# ap3036b-boost-driver-mk-1_0.net
KiCad netlist of a schematic drawn in EAGLE
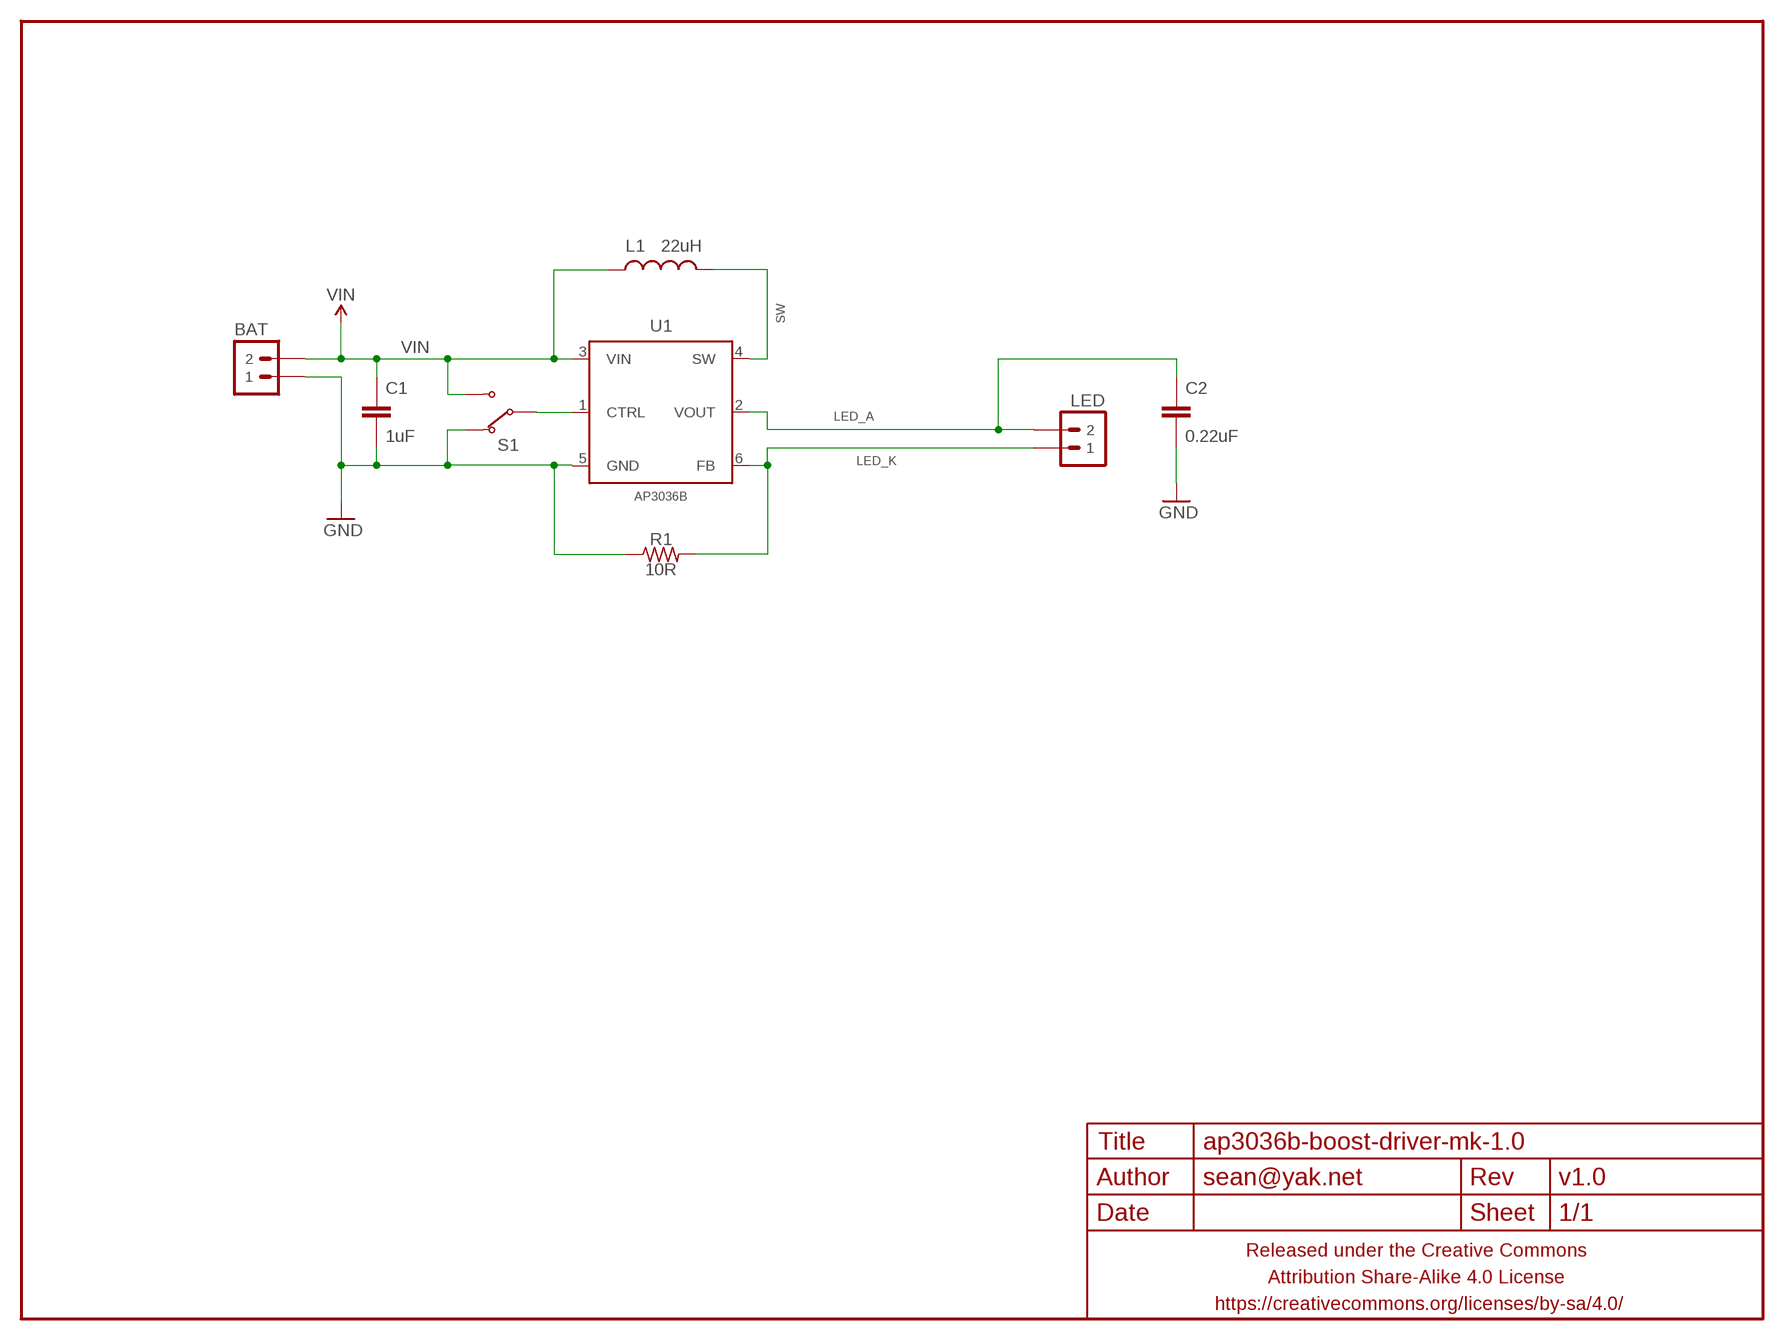
[diagram p0: schematic, sheet 1]

(export (version "E")
  (design (tool "Eeschema 10.0.6"))
  (components
    (comp (ref "BAT")
      (value "M02PTH-CENTERED")
      (footprint "eagle-import:1X02-CENTER")
      (libsource (lib "eagle-import") (part "M02PTH-CENTERED"))
    )
    (comp (ref "C1")
      (value "1uF")
      (footprint "eagle-import:C0603-TIGHTER")
      (libsource (lib "eagle-import") (part "CAPACITOR-CERAMICC0603-TIGHTER"))
    )
    (comp (ref "C2")
      (value "0.22uF")
      (footprint "eagle-import:C0603-TIGHTER")
      (libsource (lib "eagle-import") (part "CAPACITOR-CERAMICC0603-TIGHTER"))
    )
    (comp (ref "FRAME1")
      (value "FRAME-LETTERNO_PACKAGE")
      (footprint "eagle-import:DUMMY")
      (fields (field (name "DESIGNER") "sean@yak.net") (field (name "VERSION") "v1.0"))
      (libsource (lib "eagle-import") (part "FRAME-LETTERNO_PACKAGE"))
    )
    (comp (ref "L1")
      (value "22uH")
      (footprint "eagle-import:L0603")
      (libsource (lib "eagle-import") (part "INDUCTOR0603-TIGHTER"))
    )
    (comp (ref "LED")
      (value "M02PTH-CENTERED")
      (footprint "eagle-import:1X02-CENTER")
      (libsource (lib "eagle-import") (part "M02PTH-CENTERED"))
    )
    (comp (ref "R1")
      (value "10R")
      (footprint "eagle-import:R0603-TIGHTER")
      (libsource (lib "eagle-import") (part "RESISTORR0603-TIGHTER"))
    )
    (comp (ref "S1")
      (value "SWITCH-SPDTJS102011SAQN")
      (footprint "eagle-import:SWITCH-SPDT-SMD-RA-JS102011SAQN")
      (libsource (lib "eagle-import") (part "SWITCH-SPDTJS102011SAQN"))
    )
    (comp (ref "U1")
      (value "AP3036B")
      (footprint "eagle-import:SOT26")
      (libsource (lib "eagle-import") (part "AP3036B"))
    )
  )
  (nets
    (net (code "1") (name "/LED_A") (class "Default")
      (node (ref "C2") (pin "1") (pinfunction "1_1") (pintype "passive"))
      (node (ref "LED") (pin "2") (pinfunction "2_2") (pintype "passive"))
      (node (ref "U1") (pin "2") (pinfunction "VOUT_2") (pintype "bidirectional"))
    )
    (net (code "2") (name "/LED_K") (class "Default")
      (node (ref "LED") (pin "1") (pinfunction "1_1") (pintype "passive"))
      (node (ref "R1") (pin "2") (pinfunction "2_2") (pintype "passive"))
      (node (ref "U1") (pin "6") (pinfunction "FB_6") (pintype "bidirectional"))
    )
    (net (code "3") (name "/SW") (class "Default")
      (node (ref "L1") (pin "2") (pinfunction "2_2") (pintype "passive"))
      (node (ref "U1") (pin "4") (pinfunction "SW_4") (pintype "bidirectional"))
    )
    (net (code "4") (name "GND") (class "Default")
      (node (ref "BAT") (pin "1") (pinfunction "1_1") (pintype "passive"))
      (node (ref "C1") (pin "2") (pinfunction "2_2") (pintype "passive"))
      (node (ref "C2") (pin "2") (pinfunction "2_2") (pintype "passive"))
      (node (ref "R1") (pin "1") (pinfunction "1_1") (pintype "passive"))
      (node (ref "S1") (pin "3") (pinfunction "NC_3") (pintype "passive"))
      (node (ref "U1") (pin "5") (pinfunction "GND_5") (pintype "bidirectional"))
    )
    (net (code "5") (name "Net-(S1-COM)") (class "Default")
      (node (ref "S1") (pin "2") (pinfunction "COM_2") (pintype "passive"))
      (node (ref "U1") (pin "1") (pinfunction "CTRL_1") (pintype "bidirectional"))
    )
    (net (code "6") (name "VIN") (class "Default")
      (node (ref "BAT") (pin "2") (pinfunction "2_2") (pintype "passive"))
      (node (ref "C1") (pin "1") (pinfunction "1_1") (pintype "passive"))
      (node (ref "L1") (pin "1") (pinfunction "1_1") (pintype "passive"))
      (node (ref "S1") (pin "1") (pinfunction "NO_1") (pintype "passive"))
      (node (ref "U1") (pin "3") (pinfunction "VIN_3") (pintype "bidirectional"))
    )
  )
)
